# ADXL337_Breakout.net
KiCad netlist of a schematic drawn in EAGLE
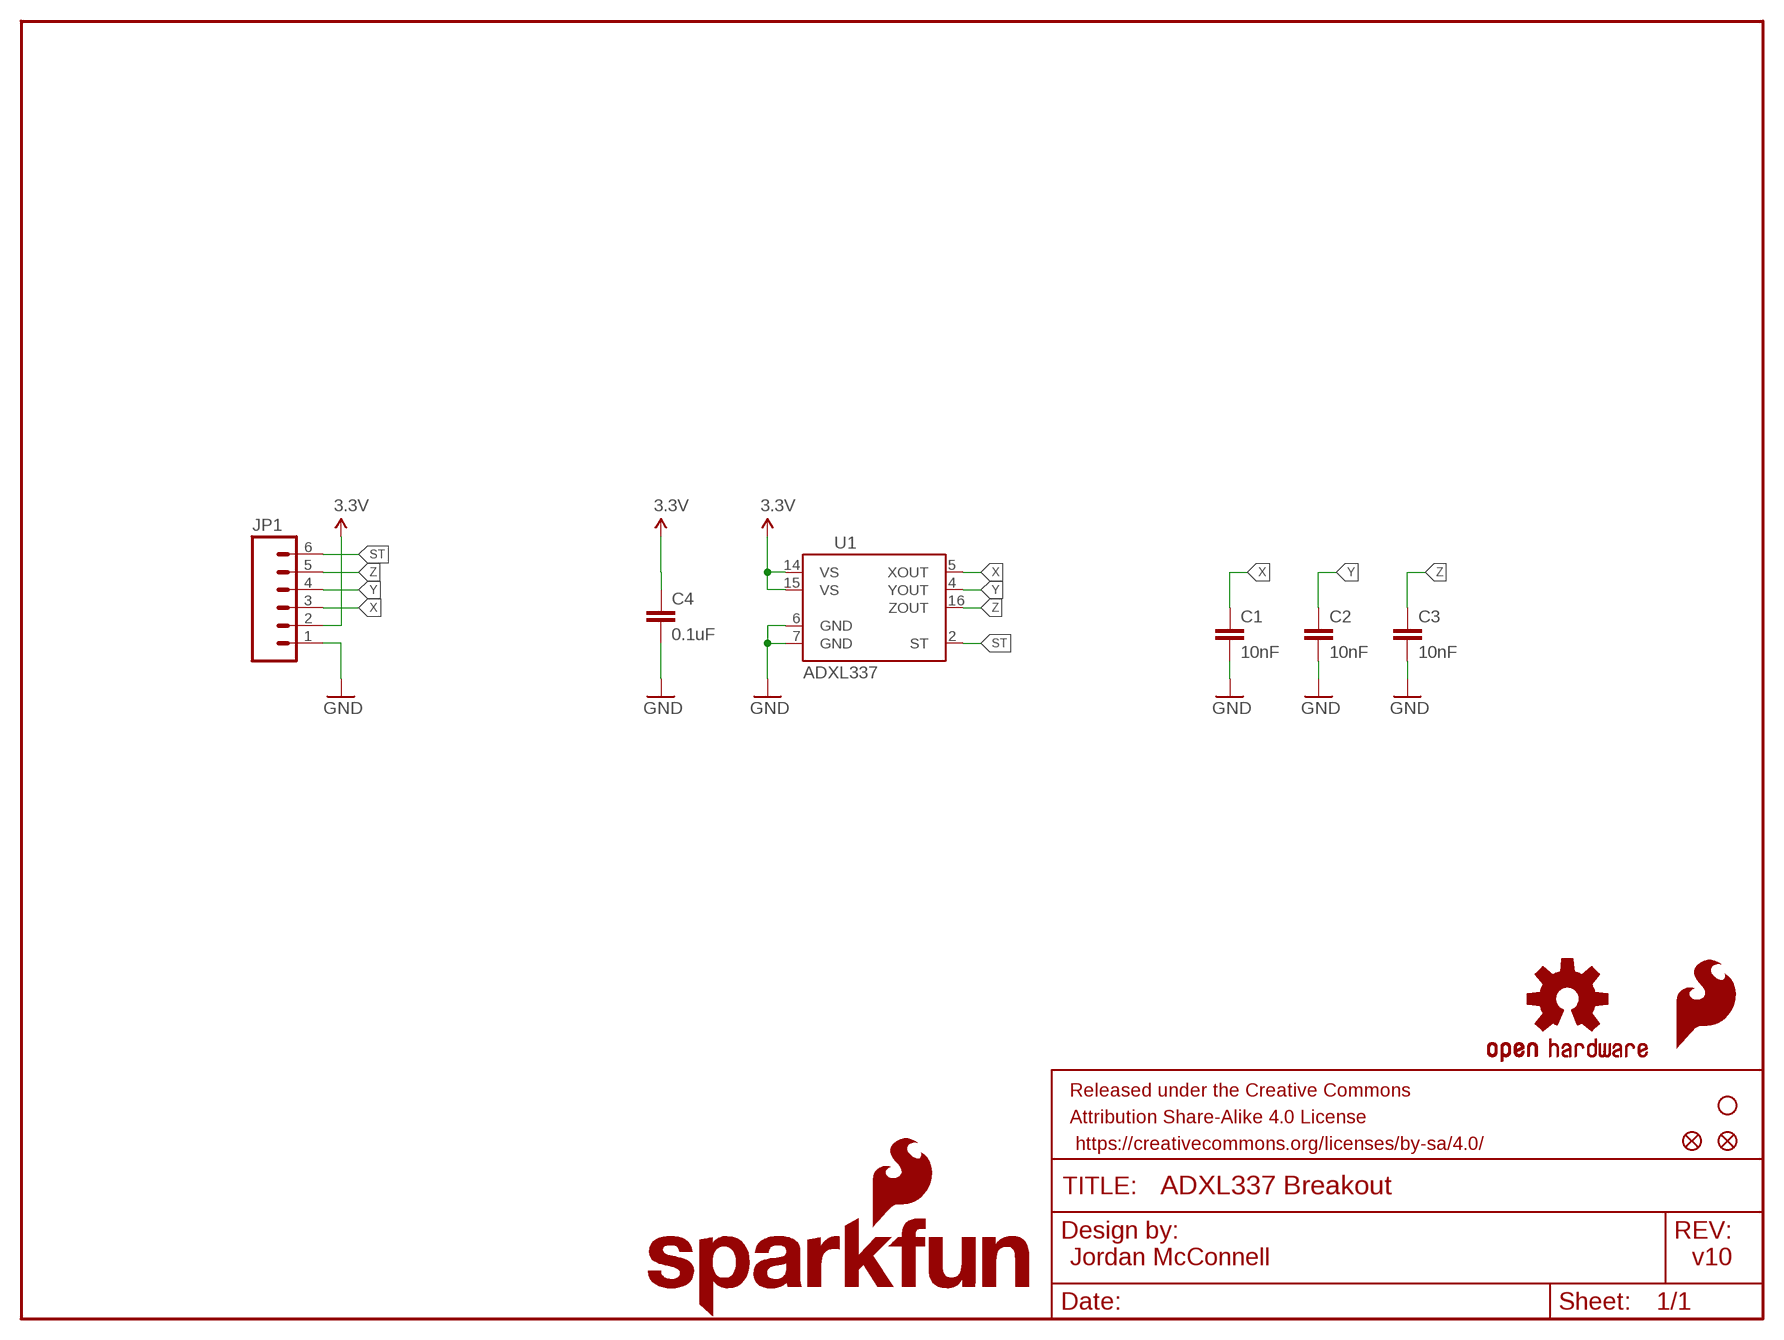
[diagram p0: schematic, sheet 1]

(export (version "E")
  (design (tool "Eeschema 10.0.6"))
  (components
    (comp (ref "C1")
      (value "10nF")
      (footprint "eagle-import:0603-CAP")
      (libsource (lib "eagle-import") (part "10NF/10000PF-50V-10%(0603)"))
    )
    (comp (ref "C2")
      (value "10nF")
      (footprint "eagle-import:0603-CAP")
      (libsource (lib "eagle-import") (part "10NF/10000PF-50V-10%(0603)"))
    )
    (comp (ref "C3")
      (value "10nF")
      (footprint "eagle-import:0603-CAP")
      (libsource (lib "eagle-import") (part "10NF/10000PF-50V-10%(0603)"))
    )
    (comp (ref "C4")
      (value "0.1uF")
      (footprint "eagle-import:0603-CAP")
      (libsource (lib "eagle-import") (part "0.1UF-25V(+80/-20%)(0603)"))
    )
    (comp (ref "FID1")
      (value "FIDUCIAL1X2")
      (footprint "eagle-import:FIDUCIAL-1X2")
      (libsource (lib "eagle-import") (part "FIDUCIAL1X2"))
    )
    (comp (ref "FID2")
      (value "FIDUCIAL1X2")
      (footprint "eagle-import:FIDUCIAL-1X2")
      (libsource (lib "eagle-import") (part "FIDUCIAL1X2"))
    )
    (comp (ref "FRAME1")
      (value "FRAME-LETTER")
      (footprint "eagle-import:CREATIVE_COMMONS")
      (libsource (lib "eagle-import") (part "FRAME-LETTER"))
    )
    (comp (ref "JP1")
      (value "M06SIP")
      (footprint "eagle-import:1X06")
      (libsource (lib "eagle-import") (part "M06SIP"))
    )
    (comp (ref "LOGO1")
      (value "SFE_LOGO_FLAME.1_INCH")
      (footprint "eagle-import:SFE_LOGO_FLAME_.1")
      (libsource (lib "eagle-import") (part "SFE_LOGO_FLAME.1_INCH"))
    )
    (comp (ref "LOGO2")
      (value "OSHW-LOGOS")
      (footprint "eagle-import:OSHW-LOGO-S")
      (libsource (lib "eagle-import") (part "OSHW-LOGOS"))
    )
    (comp (ref "LOGO3")
      (value "SFE_LOGO_NAME_FLAME.1_INCH")
      (footprint "eagle-import:SFE_LOGO_NAME_FLAME_.1")
      (libsource (lib "eagle-import") (part "SFE_LOGO_NAME_FLAME.1_INCH"))
    )
    (comp (ref "STANDOFF1")
      (value "STAND-OFF")
      (footprint "eagle-import:STAND-OFF")
      (libsource (lib "eagle-import") (part "STAND-OFF"))
    )
    (comp (ref "U1")
      (value "ADXL337")
      (footprint "eagle-import:LFCSP_LQ-16")
      (libsource (lib "eagle-import") (part "ADXL337"))
    )
  )
  (nets
    (net (code "1") (name "3.3V") (class "Default")
      (node (ref "C4") (pin "1") (pinfunction "1_1") (pintype "passive"))
      (node (ref "JP1") (pin "2") (pinfunction "2_2") (pintype "passive"))
      (node (ref "U1") (pin "14") (pinfunction "VS_14") (pintype "bidirectional"))
      (node (ref "U1") (pin "15") (pinfunction "VS_15") (pintype "bidirectional"))
    )
    (net (code "2") (name "GND") (class "Default")
      (node (ref "C1") (pin "2") (pinfunction "2_2") (pintype "passive"))
      (node (ref "C2") (pin "2") (pinfunction "2_2") (pintype "passive"))
      (node (ref "C3") (pin "2") (pinfunction "2_2") (pintype "passive"))
      (node (ref "C4") (pin "2") (pinfunction "2_2") (pintype "passive"))
      (node (ref "JP1") (pin "1") (pinfunction "1_1") (pintype "passive"))
      (node (ref "U1") (pin "6") (pinfunction "GND_6") (pintype "bidirectional"))
      (node (ref "U1") (pin "7") (pinfunction "GND_7") (pintype "bidirectional"))
    )
    (net (code "3") (name "ST") (class "Default")
      (node (ref "JP1") (pin "6") (pinfunction "6_6") (pintype "passive"))
      (node (ref "U1") (pin "2") (pinfunction "ST_2") (pintype "bidirectional"))
    )
    (net (code "4") (name "X") (class "Default")
      (node (ref "C1") (pin "1") (pinfunction "1_1") (pintype "passive"))
      (node (ref "JP1") (pin "3") (pinfunction "3_3") (pintype "passive"))
      (node (ref "U1") (pin "5") (pinfunction "XOUT_5") (pintype "bidirectional"))
    )
    (net (code "5") (name "Y") (class "Default")
      (node (ref "C2") (pin "1") (pinfunction "1_1") (pintype "passive"))
      (node (ref "JP1") (pin "4") (pinfunction "4_4") (pintype "passive"))
      (node (ref "U1") (pin "4") (pinfunction "YOUT_4") (pintype "bidirectional"))
    )
    (net (code "6") (name "Z") (class "Default")
      (node (ref "C3") (pin "1") (pinfunction "1_1") (pintype "passive"))
      (node (ref "JP1") (pin "5") (pinfunction "5_5") (pintype "passive"))
      (node (ref "U1") (pin "16") (pinfunction "ZOUT_16") (pintype "bidirectional"))
    )
  )
)
